# LMAT_AMT_V2.net
KiCad netlist of a schematic drawn in Altium Designer
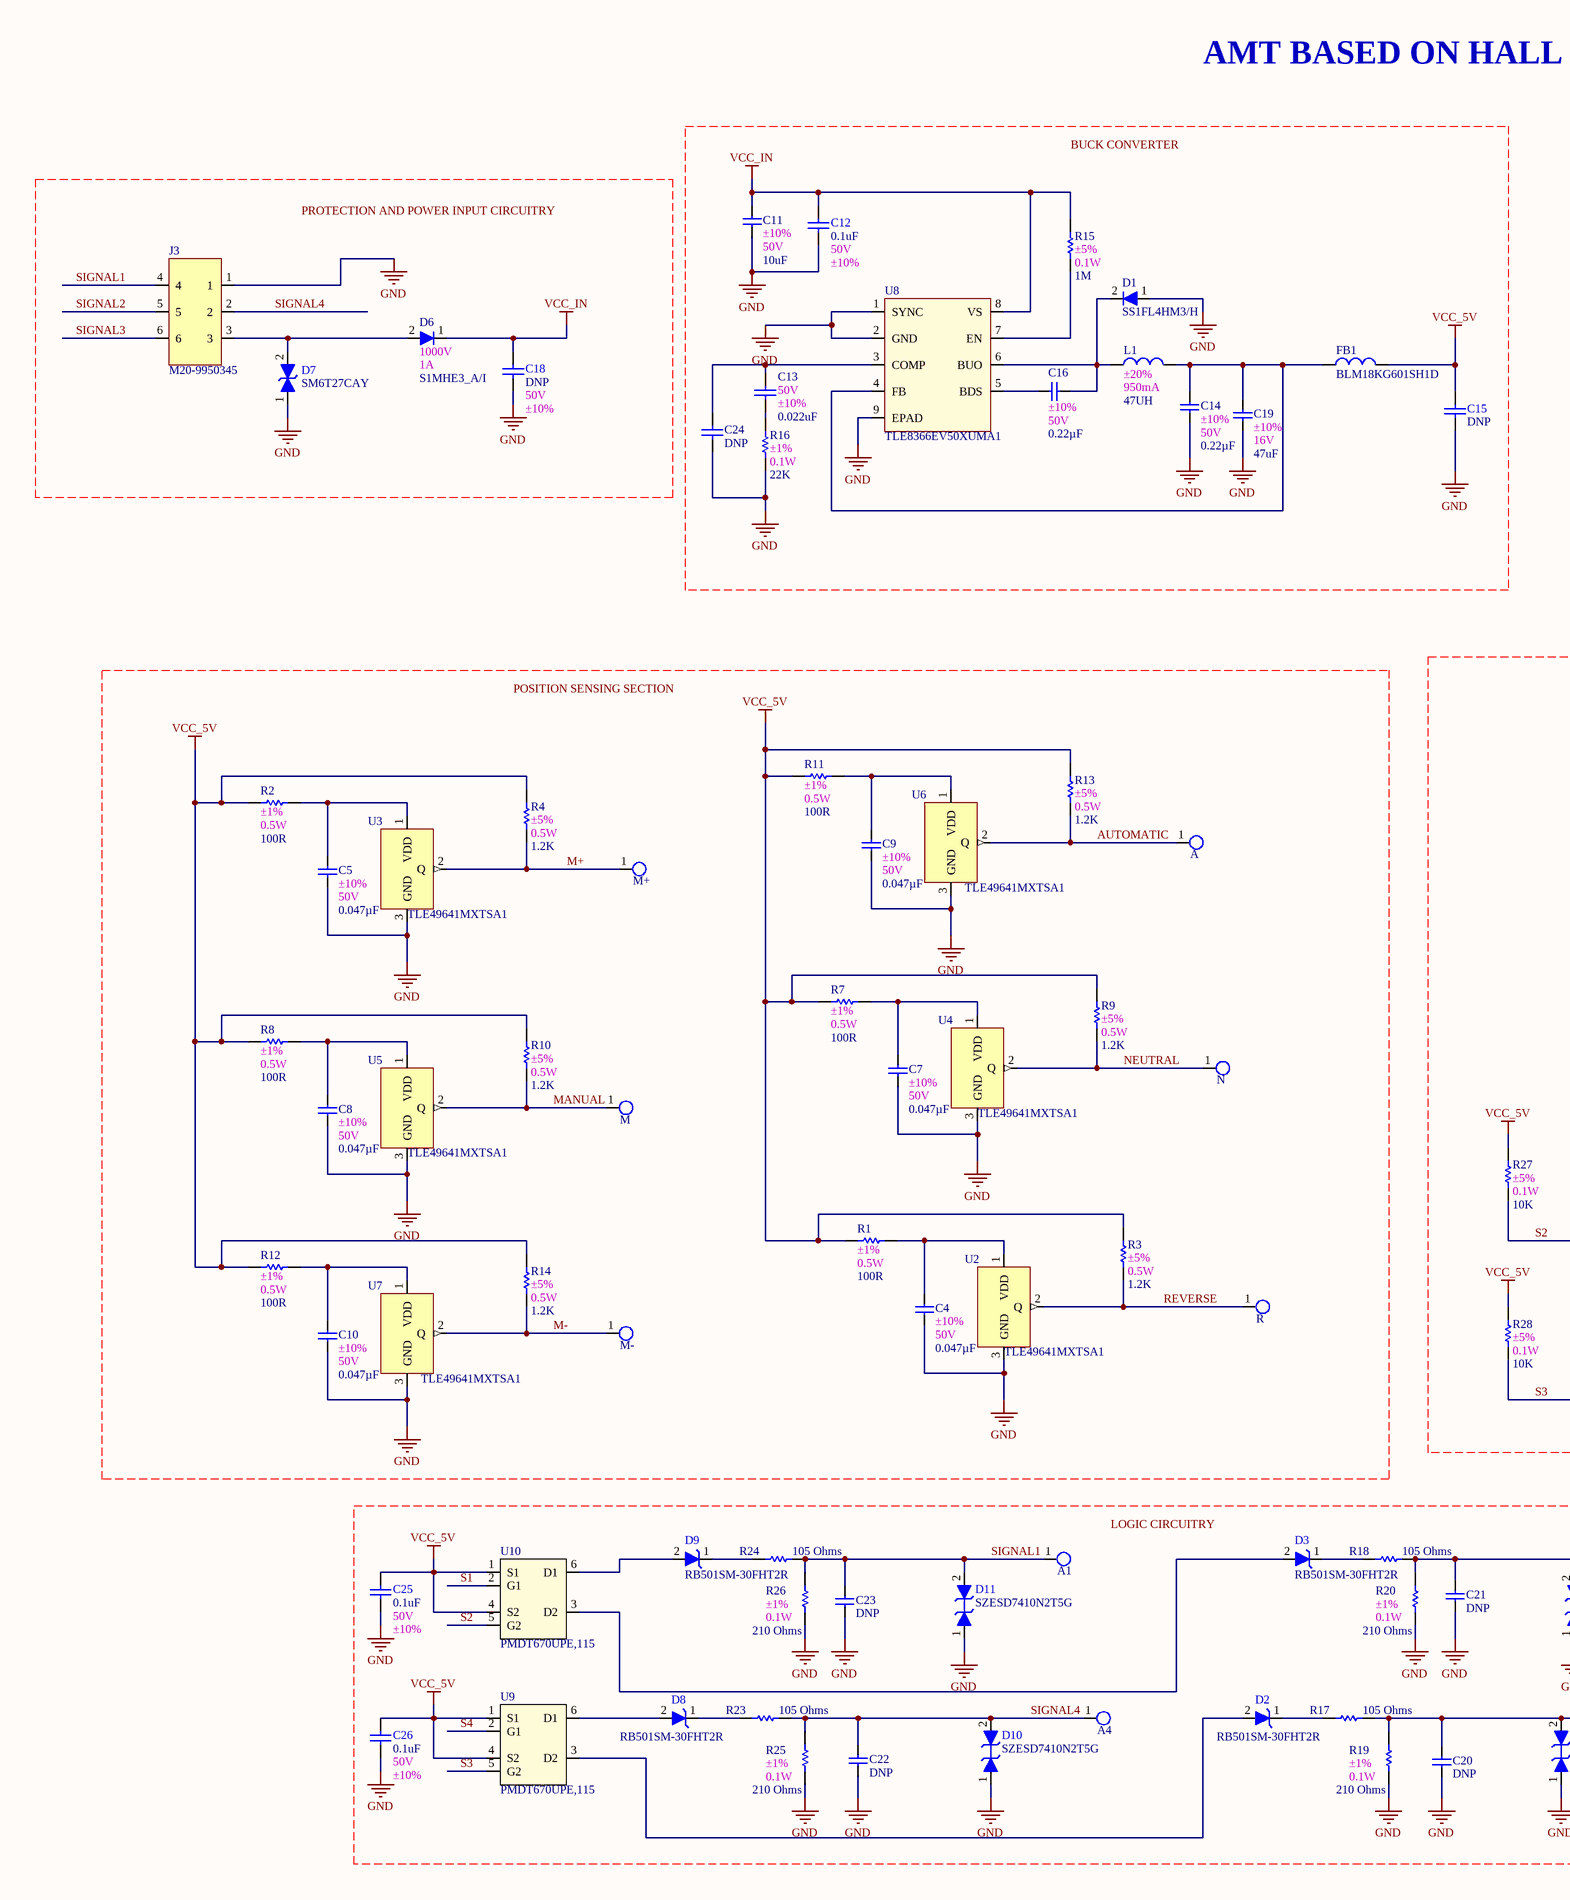
[diagram p0: LMAT_AMT_V2.SchDoc, left]
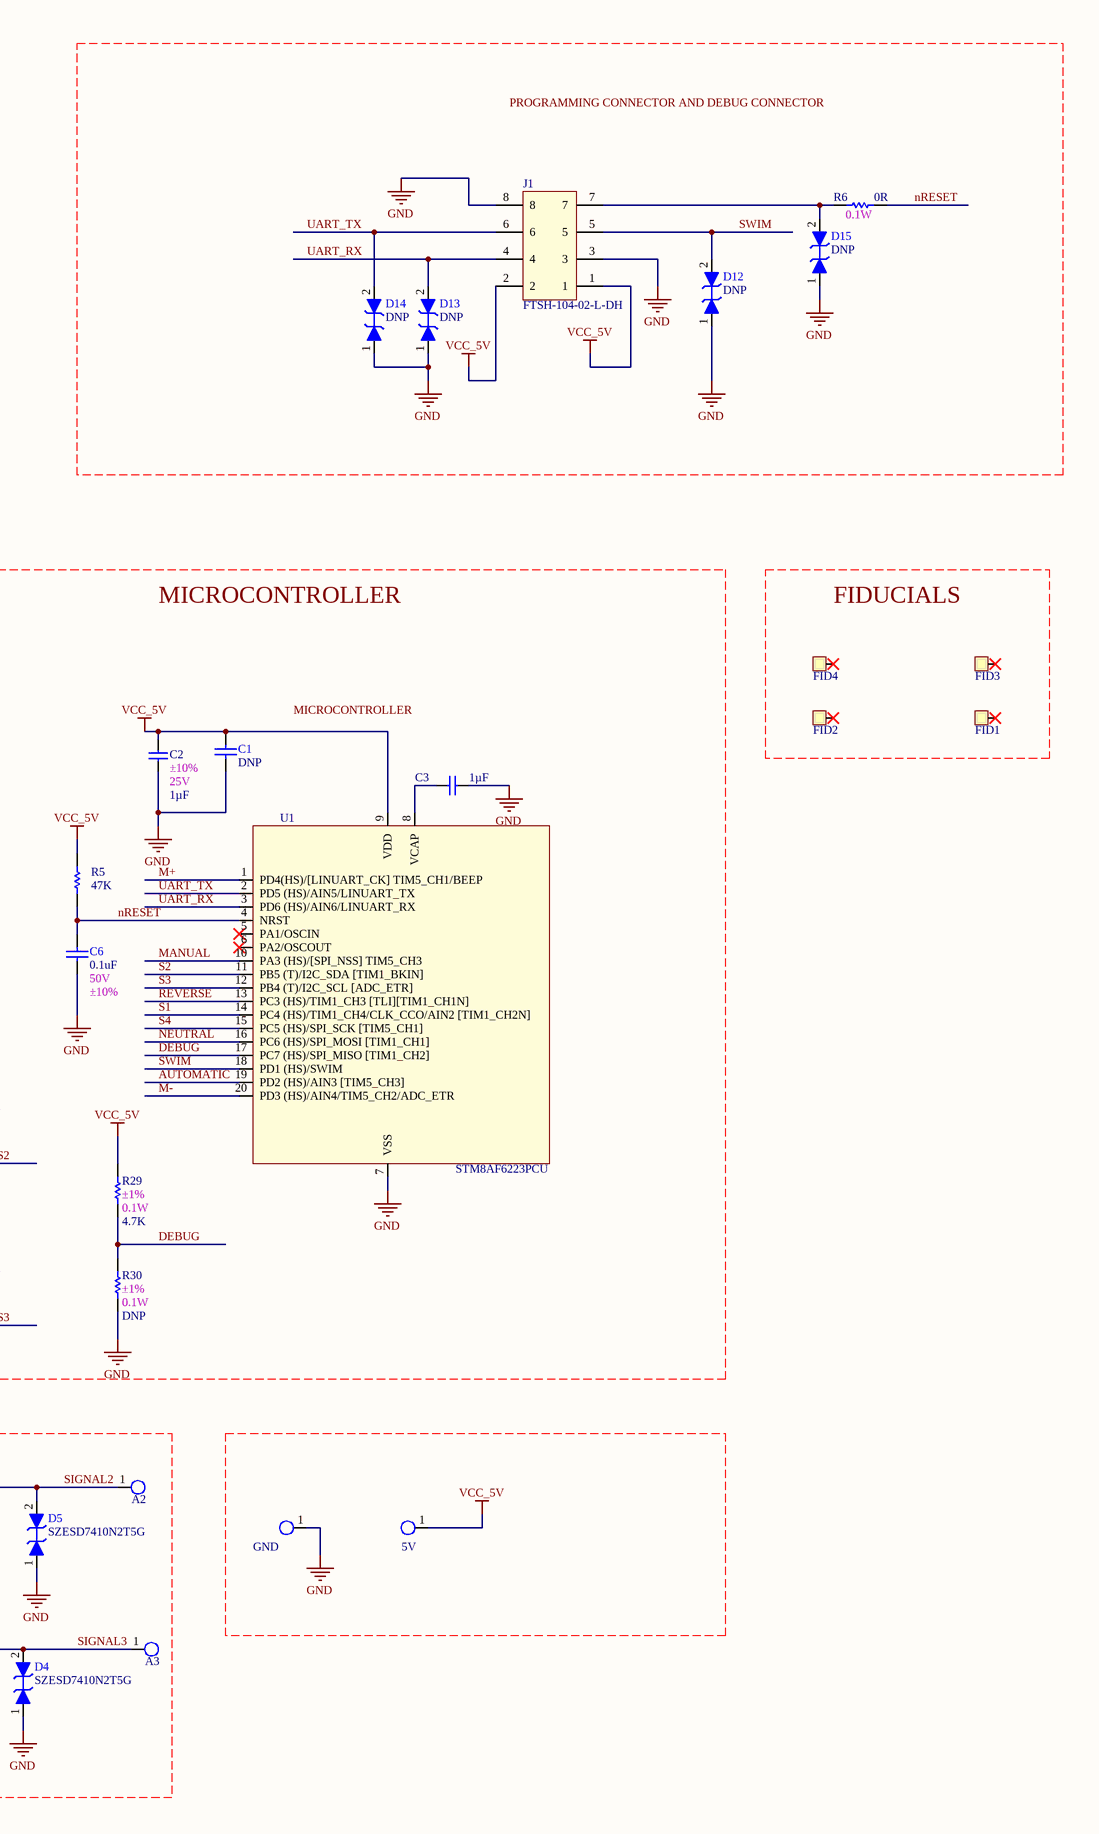
[diagram p1: LMAT_AMT_V2.SchDoc, right]

(export (version "E")
  (design (tool "Eeschema 10.0.6"))
  (components
    (comp (ref "5V")
      (value "Test Point- 35mil")
      (footprint "Integrated_Master_Library:TP_35M_DIA")
      (fields (field (name "INTERNAL PART NUMBER") "EMS-TP35MIL-S"))
      (libsource (lib "Integrated_Master_Library") (part "EMS-TP35MIL-S"))
    )
    (comp (ref "A")
      (value "Test Point- 35mil")
      (footprint "Integrated_Master_Library:TP_35M_DIA")
      (fields (field (name "INTERNAL PART NUMBER") "EMS-TP35MIL-S"))
      (libsource (lib "Integrated_Master_Library") (part "EMS-TP35MIL-S"))
    )
    (comp (ref "A1")
      (value "Test Point- 35mil")
      (footprint "Integrated_Master_Library:TP_35M_DIA")
      (fields (field (name "INTERNAL PART NUMBER") "EMS-TP35MIL-S"))
      (libsource (lib "Integrated_Master_Library") (part "EMS-TP35MIL-S"))
    )
    (comp (ref "A2")
      (value "Test Point- 35mil")
      (footprint "Integrated_Master_Library:TP_35M_DIA")
      (fields (field (name "INTERNAL PART NUMBER") "EMS-TP35MIL-S"))
      (libsource (lib "Integrated_Master_Library") (part "EMS-TP35MIL-S"))
    )
    (comp (ref "A3")
      (value "Test Point- 35mil")
      (footprint "Integrated_Master_Library:TP_35M_DIA")
      (fields (field (name "INTERNAL PART NUMBER") "EMS-TP35MIL-S"))
      (libsource (lib "Integrated_Master_Library") (part "EMS-TP35MIL-S"))
    )
    (comp (ref "A4")
      (value "Test Point- 35mil")
      (footprint "Integrated_Master_Library:TP_35M_DIA")
      (fields (field (name "INTERNAL PART NUMBER") "EMS-TP35MIL-S"))
      (libsource (lib "Integrated_Master_Library") (part "EMS-TP35MIL-S"))
    )
    (comp (ref "C1")
      (value "DNP")
      (footprint "SMDC0603")
      (description "CAP CER 0.1UF 50V 10% X7R 0603")
      (fields
        (field (name "MANUFACTURER PART NUMBER") "CGA3E2X7R1H104K080AA")
        (field (name "MANUFACTURER") "TDK Corporation")
      )
      (libsource (lib "Integrated_Master_Library") (part "ECA0U10K50V0-SC"))
    )
    (comp (ref "C2")
      (value "1µF")
      (footprint "Automobile-ML:SMDC0603")
      (description "CAP CER 1UF 25V X7R 0603")
      (fields
        (field (name "MANUFACTURER") "TDK Corporation")
        (field (name "VENDOR PART NUMBER") "445-173628-1-ND")
        (field (name "2ND AUXILIARY FIELD") "±10%")
        (field (name "1ST AUXILIARY FIELD") "25V")
      )
      (libsource (lib "Integrated_Master_Library (3)") (part "ECA1U00L25V0-SC"))
    )
    (comp (ref "C3")
      (value "1µF")
      (footprint "Automobile-ML:SMDC0603")
      (description "CAP CER 1UF 25V X7R 0603")
      (fields
        (field (name "MANUFACTURER") "TDK Corporation")
        (field (name "VENDOR PART NUMBER") "445-173628-1-ND")
      )
      (libsource (lib "Integrated_Master_Library (3)") (part "ECA1U00L25V0-SC"))
    )
    (comp (ref "C4")
      (value "0.047µF")
      (footprint "SMDC0603")
      (description "CAP CER 0.047UF 50V X7R 0603")
      (fields
        (field (name "MANUFACTURER") "TDK Corporation")
        (field (name "VENDOR PART NUMBER") "445-5664-1-ND")
        (field (name "2ND AUXILIARY FIELD") "±10%")
        (field (name "1ST AUXILIARY FIELD") "50V")
      )
      (libsource (lib "Integrated_Master_Library") (part "ECA47N0L50V-SC"))
    )
    (comp (ref "C5")
      (value "0.047µF")
      (footprint "SMDC0603")
      (description "CAP CER 0.047UF 50V X7R 0603")
      (fields
        (field (name "MANUFACTURER") "TDK Corporation")
        (field (name "VENDOR PART NUMBER") "445-5664-1-ND")
        (field (name "2ND AUXILIARY FIELD") "±10%")
        (field (name "1ST AUXILIARY FIELD") "50V")
      )
      (libsource (lib "Integrated_Master_Library") (part "ECA47N0L50V-SC"))
    )
    (comp (ref "C6")
      (value "0.1uF")
      (footprint "SMDC0603")
      (description "CAP CER 0.1UF 50V 10% X7R 0603")
      (fields
        (field (name "MANUFACTURER PART NUMBER") "CGA3E2X7R1H104K080AA")
        (field (name "MANUFACTURER") "TDK Corporation")
        (field (name "1ST AUXILIARY FIELD") "50V")
        (field (name "2ND AUXILIARY FIELD") "±10%")
      )
      (libsource (lib "Integrated_Master_Library") (part "ECA0U10K50V0-SC"))
    )
    (comp (ref "C7")
      (value "0.047µF")
      (footprint "SMDC0603")
      (description "CAP CER 0.047UF 50V X7R 0603")
      (fields
        (field (name "MANUFACTURER") "TDK Corporation")
        (field (name "VENDOR PART NUMBER") "445-5664-1-ND")
        (field (name "2ND AUXILIARY FIELD") "±10%")
        (field (name "1ST AUXILIARY FIELD") "50V")
      )
      (libsource (lib "Integrated_Master_Library") (part "ECA47N0L50V-SC"))
    )
    (comp (ref "C8")
      (value "0.047µF")
      (footprint "SMDC0603")
      (description "CAP CER 0.047UF 50V X7R 0603")
      (fields
        (field (name "MANUFACTURER") "TDK Corporation")
        (field (name "VENDOR PART NUMBER") "445-5664-1-ND")
        (field (name "2ND AUXILIARY FIELD") "±10%")
        (field (name "1ST AUXILIARY FIELD") "50V")
      )
      (libsource (lib "Integrated_Master_Library") (part "ECA47N0L50V-SC"))
    )
    (comp (ref "C9")
      (value "0.047µF")
      (footprint "SMDC0603")
      (description "CAP CER 0.047UF 50V X7R 0603")
      (fields
        (field (name "MANUFACTURER") "TDK Corporation")
        (field (name "VENDOR PART NUMBER") "445-5664-1-ND")
        (field (name "2ND AUXILIARY FIELD") "±10%")
        (field (name "1ST AUXILIARY FIELD") "50V")
      )
      (libsource (lib "Integrated_Master_Library") (part "ECA47N0L50V-SC"))
    )
    (comp (ref "C10")
      (value "0.047µF")
      (footprint "SMDC0603")
      (description "CAP CER 0.047UF 50V X7R 0603")
      (fields
        (field (name "MANUFACTURER") "TDK Corporation")
        (field (name "VENDOR PART NUMBER") "445-5664-1-ND")
        (field (name "2ND AUXILIARY FIELD") "±10%")
        (field (name "1ST AUXILIARY FIELD") "50V")
      )
      (libsource (lib "Integrated_Master_Library") (part "ECA47N0L50V-SC"))
    )
    (comp (ref "C11")
      (value "10uF")
      (footprint "Integrated_Master_Library:SMDC1210")
      (description "CAP CER 10UF 50V X7R 1210")
      (fields
        (field (name "MANUFACTURER") "Taiyo Yuden")
        (field (name "VENDOR PART NUMBER") "587-6026-1-ND")
        (field (name "2ND AUXILIARY FIELD") "±10%")
        (field (name "1ST AUXILIARY FIELD") "50V")
      )
      (libsource (lib "AMT") (part "ECA10U0L50V0-SH"))
    )
    (comp (ref "C12")
      (value "0.1uF")
      (footprint "SMDC0603")
      (description "CAP CER 0.1UF 50V 10% X7R 0603")
      (fields
        (field (name "MANUFACTURER PART NUMBER") "CGA3E2X7R1H104K080AA")
        (field (name "MANUFACTURER") "TDK Corporation")
        (field (name "1ST AUXILIARY FIELD") "50V")
        (field (name "2ND AUXILIARY FIELD") "±10%")
      )
      (libsource (lib "Integrated_Master_Library") (part "ECA0U10K50V0-SC"))
    )
    (comp (ref "C13")
      (value "0.022uF")
      (footprint "SMDC0603")
      (description "CAP CER 0.022UF 50V 10% X7R 0603")
      (fields
        (field (name "MANUFACTURER PART NUMBER") "CGA3E2X7R1H223K080AA")
        (field (name "MANUFACTURER") "TDK Corporation")
        (field (name "1ST AUXILIARY FIELD") "50V")
        (field (name "2ND AUXILIARY FIELD") "±10%")
      )
      (libsource (lib "Integrated_Master_Library") (part "ECA0U022K50V0-SC"))
    )
    (comp (ref "C14")
      (value "0.22µF")
      (footprint "Automobile-ML:SMDC0603")
      (description "CAP CER 0.22UF 50V X7R 0603")
      (fields
        (field (name "MANUFACTURER") "Murata Electronics North America")
        (field (name "VENDOR PART NUMBER") "490-14410-1-ND")
        (field (name "2ND AUXILIARY FIELD") "±10%")
        (field (name "1ST AUXILIARY FIELD") "50V")
      )
      (libsource (lib "Integrated_Master_Library (3)") (part "ECA0U22L50V0-SC"))
    )
    (comp (ref "C15")
      (value "DNP")
      (footprint "SMDC0603")
      (description "CAP CER 0.1UF 50V 10% X7R 0603")
      (fields
        (field (name "MANUFACTURER PART NUMBER") "CGA3E2X7R1H104K080AA")
        (field (name "MANUFACTURER") "TDK Corporation")
      )
      (libsource (lib "Integrated_Master_Library") (part "ECA0U10K50V0-SC"))
    )
    (comp (ref "C16")
      (value "0.22µF")
      (footprint "SMDC0603")
      (description "CAP CER 0.22UF 50V X7R 0603")
      (fields
        (field (name "MANUFACTURER") "Murata Electronics North America")
        (field (name "VENDOR PART NUMBER") "490-14410-1-ND")
        (field (name "2ND AUXILIARY FIELD") "±10%")
        (field (name "1ST AUXILIARY FIELD") "50V")
      )
      (libsource (lib "Integrated_Master_Library") (part "ECA0U22L50V0-SC"))
    )
    (comp (ref "C18")
      (value "DNP")
      (footprint "SMDC0603")
      (description "CAP CER 0.1UF 50V 10% X7R 0603")
      (fields
        (field (name "MANUFACTURER PART NUMBER") "CGA3E2X7R1H104K080AA")
        (field (name "MANUFACTURER") "TDK Corporation")
        (field (name "1ST AUXILIARY FIELD") "50V")
        (field (name "2ND AUXILIARY FIELD") "±10%")
      )
      (libsource (lib "Integrated_Master_Library") (part "ECA0U10K50V0-SC"))
    )
    (comp (ref "C19")
      (value "47uF")
      (footprint "SMDC1210")
      (description "CAP CER 47UF 16V X6S 1210")
      (fields
        (field (name "MANUFACTURER") "Murata Electronics North America")
        (field (name "VENDOR PART NUMBER") "490-12494-1-ND")
        (field (name "2ND AUXILIARY FIELD") "±10%")
        (field (name "1ST AUXILIARY FIELD") "16V")
      )
      (libsource (lib "Automobile-ML") (part "ECA47U0L16V0-SH"))
    )
    (comp (ref "C20")
      (value "DNP")
      (footprint "SMDC0603")
      (description "CAP CER 10000PF 50V X8R 0603")
      (fields
        (field (name "MANUFACTURER") "TDK Corporation")
        (field (name "VENDOR PART NUMBER") "445-5892-1-ND")
      )
      (libsource (lib "Automobile-ML") (part "ECA0U01L50V0-SC"))
    )
    (comp (ref "C21")
      (value "DNP")
      (footprint "SMDC0603")
      (description "CAP CER 10000PF 50V X8R 0603")
      (fields
        (field (name "MANUFACTURER") "TDK Corporation")
        (field (name "VENDOR PART NUMBER") "445-5892-1-ND")
      )
      (libsource (lib "Automobile-ML") (part "ECA0U01L50V0-SC"))
    )
    (comp (ref "C22")
      (value "DNP")
      (footprint "SMDC0603")
      (description "CAP CER 10000PF 50V X8R 0603")
      (fields
        (field (name "MANUFACTURER") "TDK Corporation")
        (field (name "VENDOR PART NUMBER") "445-5892-1-ND")
      )
      (libsource (lib "Automobile-ML") (part "ECA0U01L50V0-SC"))
    )
    (comp (ref "C23")
      (value "DNP")
      (footprint "SMDC0603")
      (description "CAP CER 10000PF 50V X8R 0603")
      (fields
        (field (name "MANUFACTURER") "TDK Corporation")
        (field (name "VENDOR PART NUMBER") "445-5892-1-ND")
      )
      (libsource (lib "Automobile-ML") (part "ECA0U01L50V0-SC"))
    )
    (comp (ref "C24")
      (value "DNP")
      (footprint "SMDC0603")
      (description "CAP CER 0.022UF 50V 10% X7R 0603")
      (fields
        (field (name "MANUFACTURER PART NUMBER") "CGA3E2X7R1H223K080AA")
        (field (name "MANUFACTURER") "TDK Corporation")
      )
      (libsource (lib "Integrated_Master_Library") (part "ECA0U022K50V0-SC"))
    )
    (comp (ref "C25")
      (value "0.1uF")
      (footprint "SMDC0603")
      (description "CAP CER 0.1UF 50V 10% X7R 0603")
      (fields
        (field (name "MANUFACTURER PART NUMBER") "CGA3E2X7R1H104K080AA")
        (field (name "MANUFACTURER") "TDK Corporation")
        (field (name "1ST AUXILIARY FIELD") "50V")
        (field (name "2ND AUXILIARY FIELD") "±10%")
      )
      (libsource (lib "Integrated_Master_Library") (part "ECA0U10K50V0-SC"))
    )
    (comp (ref "C26")
      (value "0.1uF")
      (footprint "SMDC0603")
      (description "CAP CER 0.1UF 50V 10% X7R 0603")
      (fields
        (field (name "MANUFACTURER PART NUMBER") "CGA3E2X7R1H104K080AA")
        (field (name "MANUFACTURER") "TDK Corporation")
        (field (name "1ST AUXILIARY FIELD") "50V")
        (field (name "2ND AUXILIARY FIELD") "±10%")
      )
      (libsource (lib "Integrated_Master_Library") (part "ECA0U10K50V0-SC"))
    )
    (comp (ref "D1")
      (value "SS1FL4HM3/H")
      (footprint "Integrated_Master_Library:SODFL370X110-2N")
      (description "DIODE SCHOTTKY 40V 1A DO-219AB")
      (fields
        (field (name "MANUFACTURER") "Vishay Semiconductor Diodes Division")
        (field (name "INTERNAL PART NUMBER") "EDDVS1A0040V0-S")
      )
      (libsource (lib "Integrated_Master_Library (3)") (part "EDDVS1A0040V0-S"))
    )
    (comp (ref "D2")
      (value "RB501SM-30FHT2R")
      (footprint "Integrated_Master_Library:SOD1700X70N-V2")
      (description "Diode Schottky 30V 100mA Surface Mount EMD2")
      (fields
        (field (name "MANUFACTURER") "Rohm Semiconductor")
        (field (name "INTERNAL PART NUMBER") "EDDR0A1030V0-S")
      )
      (libsource (lib "Integrated_Master_Library (3)") (part "EDDR0A1030V0-S"))
    )
    (comp (ref "D3")
      (value "RB501SM-30FHT2R")
      (footprint "Integrated_Master_Library:SOD1700X70N-V2")
      (description "Diode Schottky 30V 100mA Surface Mount EMD2")
      (fields
        (field (name "MANUFACTURER") "Rohm Semiconductor")
        (field (name "INTERNAL PART NUMBER") "EDDR0A1030V0-S")
      )
      (libsource (lib "Integrated_Master_Library (3)") (part "EDDR0A1030V0-S"))
    )
    (comp (ref "D4")
      (value "SZESD7410N2T5G")
      (footprint "DFN65P100X65X45-2N")
      (description "TVS DIODE 8V 20V 2X2DFN")
      (fields
        (field (name "MANUFACTURER") "ON Semiconductor")
        (field (name "INTERNAL PART NUMBER") "EDDOS16A010V0-S")
      )
      (libsource (lib "Automobile-ML") (part "EDDOS16A010V0-S"))
    )
    (comp (ref "D5")
      (value "SZESD7410N2T5G")
      (footprint "DFN65P100X65X45-2N")
      (description "TVS DIODE 8V 20V 2X2DFN")
      (fields
        (field (name "MANUFACTURER") "ON Semiconductor")
        (field (name "INTERNAL PART NUMBER") "EDDOS16A010V0-S")
      )
      (libsource (lib "Automobile-ML") (part "EDDOS16A010V0-S"))
    )
    (comp (ref "D6")
      (value "S1MHE3_A/I")
      (footprint "Integrated_Master_Library:DIOM4227X23N-2N")
      (description "DIODE GEN PURP 1KV 1A DO214AC")
      (fields
        (field (name "MANUFACTURER") "Vishay Semiconductor Diodes Division")
        (field (name "INTERNAL PART NUMBER") "EDDVS1A001000V-S")
        (field (name "1ST AUXILIARY FIELD") "1000V")
        (field (name "2ND AUXILIARY FIELD") "1A")
      )
      (libsource (lib "Integrated_Master_Library") (part "EDDVS1A001000V-S"))
    )
    (comp (ref "D7")
      (value "SM6T27CAY")
      (footprint "DIOM4336X26B")
      (description "TVS DIODE 23.1V 48.3V SMB")
      (fields
        (field (name "MANUFACTURER") "STMicroelectronics")
        (field (name "INTERNAL PART NUMBER") "EDDST83A025V7-S")
      )
      (libsource (lib "Integrated_Master_Library") (part "EDDST83A025V7-S"))
    )
    (comp (ref "D8")
      (value "RB501SM-30FHT2R")
      (footprint "Integrated_Master_Library:SOD1700X70N-V2")
      (description "Diode Schottky 30V 100mA Surface Mount EMD2")
      (fields
        (field (name "MANUFACTURER") "Rohm Semiconductor")
        (field (name "INTERNAL PART NUMBER") "EDDR0A1030V0-S")
      )
      (libsource (lib "Integrated_Master_Library (3)") (part "EDDR0A1030V0-S"))
    )
    (comp (ref "D9")
      (value "RB501SM-30FHT2R")
      (footprint "Integrated_Master_Library:SOD1700X70N-V2")
      (description "Diode Schottky 30V 100mA Surface Mount EMD2")
      (fields
        (field (name "MANUFACTURER") "Rohm Semiconductor")
        (field (name "INTERNAL PART NUMBER") "EDDR0A1030V0-S")
      )
      (libsource (lib "Integrated_Master_Library (3)") (part "EDDR0A1030V0-S"))
    )
    (comp (ref "D10")
      (value "SZESD7410N2T5G")
      (footprint "DFN65P100X65X45-2N")
      (description "TVS DIODE 8V 20V 2X2DFN")
      (fields
        (field (name "MANUFACTURER") "ON Semiconductor")
        (field (name "INTERNAL PART NUMBER") "EDDOS16A010V0-S")
      )
      (libsource (lib "Automobile-ML") (part "EDDOS16A010V0-S"))
    )
    (comp (ref "D11")
      (value "SZESD7410N2T5G")
      (footprint "DFN65P100X65X45-2N")
      (description "TVS DIODE 8V 20V 2X2DFN")
      (fields
        (field (name "MANUFACTURER") "ON Semiconductor")
        (field (name "INTERNAL PART NUMBER") "EDDOS16A010V0-S")
      )
      (libsource (lib "Automobile-ML") (part "EDDOS16A010V0-S"))
    )
    (comp (ref "D12")
      (value "DNP")
      (footprint "DFN65P100X65X45-2N")
      (description "TVS DIODE 8V 20V 2X2DFN")
      (fields
        (field (name "MANUFACTURER PART NUMBER") "SZESD7410N2T5G")
        (field (name "MANUFACTURER") "ON Semiconductor")
      )
      (libsource (lib "Automobile-ML") (part "EDDOS16A010V0-S"))
    )
    (comp (ref "D13")
      (value "DNP")
      (footprint "DFN65P100X65X45-2N")
      (description "TVS DIODE 8V 20V 2X2DFN")
      (fields
        (field (name "MANUFACTURER PART NUMBER") "SZESD7410N2T5G")
        (field (name "MANUFACTURER") "ON Semiconductor")
      )
      (libsource (lib "Automobile-ML") (part "EDDOS16A010V0-S"))
    )
    (comp (ref "D14")
      (value "DNP")
      (footprint "DFN65P100X65X45-2N")
      (description "TVS DIODE 8V 20V 2X2DFN")
      (fields
        (field (name "MANUFACTURER PART NUMBER") "SZESD7410N2T5G")
        (field (name "MANUFACTURER") "ON Semiconductor")
      )
      (libsource (lib "Automobile-ML") (part "EDDOS16A010V0-S"))
    )
    (comp (ref "D15")
      (value "DNP")
      (footprint "DFN65P100X65X45-2N")
      (description "TVS DIODE 8V 20V 2X2DFN")
      (fields
        (field (name "MANUFACTURER PART NUMBER") "SZESD7410N2T5G")
        (field (name "MANUFACTURER") "ON Semiconductor")
      )
      (libsource (lib "Automobile-ML") (part "EDDOS16A010V0-S"))
    )
    (comp (ref "FB1")
      (value "BLM18KG601SH1D")
      (footprint "Integrated_Master_Library:SMDL0603")
      (description "FERRITE BEAD 600 OHM 0603 1LN")
      (fields
        (field (name "MANUFACTURER") "Murata Electronics North America")
        (field (name "VENDOR PART NUMBER") "490-13259-1-ND")
      )
      (libsource (lib "Automobile-ML") (part "EIN600R1A30-S"))
    )
    (comp (ref "FID1")
      (value "FID40X40")
      (footprint "FID40X40")
      (libsource (lib "Integrated_Master_Library") (part "FID_40X40"))
    )
    (comp (ref "FID2")
      (value "FID40X40")
      (footprint "FID40X40")
      (libsource (lib "Integrated_Master_Library") (part "FID_40X40"))
    )
    (comp (ref "FID3")
      (value "FID40X40")
      (footprint "FID40X40")
      (libsource (lib "Integrated_Master_Library") (part "FID_40X40"))
    )
    (comp (ref "FID4")
      (value "FID40X40")
      (footprint "FID40X40")
      (libsource (lib "Integrated_Master_Library") (part "FID_40X40"))
    )
    (comp (ref "GND")
      (value "Test Point- 35mil")
      (footprint "Integrated_Master_Library:TP_35M_DIA")
      (fields (field (name "INTERNAL PART NUMBER") "EMS-TP35MIL-S"))
      (libsource (lib "Integrated_Master_Library") (part "EMS-TP35MIL-S"))
    )
    (comp (ref "J1")
      (value "CONN HEADER R/A 6POS 2.54MMCONN HEADER SMD R/A 8POS 1.27MM")
      (footprint "HDRRA8W53P127_2X4_9754X251X343P")
      (description "CONN HEADER SMD R/A 8POS 1.27MM")
      (fields
        (field (name "MANUFACTURER") "Samtec Inc.")
        (field (name "INTERNAL PART NUMBER") "ECN-FTSH-104-02-L-DH-0005")
        (field (name "MANUFACTURER PART NUMBER") "FTSH-104-02-L-DH")
      )
      (libsource (lib "Automobile-ML") (part "ECN-FTSH-104-02-L-DH-0005"))
    )
    (comp (ref "J3")
      (value "CONN HEADER R/A 6POS 2.54MM")
      (footprint "HDRRA6W86P254_2X3_1344X254X528P")
      (fields
        (field (name "MANUFACTURER") "Harwin Inc.")
        (field (name "INTERNAL PART NUMBER") "ECN-M20-9950345-0003")
        (field (name "VENDOR PART NUMBER") "952-2092-ND")
        (field (name "MANUFACTURER PART NUMBER") "M20-9950345")
      )
      (libsource (lib "Automobile-ML") (part "ECN-M20-9950345-0003"))
    )
    (comp (ref "L1")
      (value "47UH")
      (footprint "Integrated_Master_Library:INDC4949X310N")
      (description "FIXED IND 47UH 700MA 422.5 MOHM")
      (fields
        (field (name "MANUFACTURER") "Taiyo Yuden")
        (field (name "VENDOR PART NUMBER") "587-3604-1-ND")
        (field (name "2ND AUXILIARY FIELD") "±20%")
        (field (name "1ST AUXILIARY FIELD") "950mA")
      )
      (libsource (lib "AMT") (part "EIN47U0N950M-S"))
    )
    (comp (ref "M")
      (value "Test Point- 35mil")
      (footprint "Integrated_Master_Library:TP_35M_DIA")
      (fields (field (name "INTERNAL PART NUMBER") "EMS-TP35MIL-S"))
      (libsource (lib "Integrated_Master_Library") (part "EMS-TP35MIL-S"))
    )
    (comp (ref "M+")
      (value "Test Point- 35mil")
      (footprint "Integrated_Master_Library:TP_35M_DIA")
      (fields (field (name "INTERNAL PART NUMBER") "EMS-TP35MIL-S"))
      (libsource (lib "Integrated_Master_Library") (part "EMS-TP35MIL-S"))
    )
    (comp (ref "M-")
      (value "Test Point- 35mil")
      (footprint "Integrated_Master_Library:TP_35M_DIA")
      (fields (field (name "INTERNAL PART NUMBER") "EMS-TP35MIL-S"))
      (libsource (lib "Integrated_Master_Library") (part "EMS-TP35MIL-S"))
    )
    (comp (ref "N")
      (value "Test Point- 35mil")
      (footprint "Integrated_Master_Library:TP_35M_DIA")
      (fields (field (name "INTERNAL PART NUMBER") "EMS-TP35MIL-S"))
      (libsource (lib "Integrated_Master_Library") (part "EMS-TP35MIL-S"))
    )
    (comp (ref "R")
      (value "Test Point- 35mil")
      (footprint "Integrated_Master_Library:TP_35M_DIA")
      (fields (field (name "INTERNAL PART NUMBER") "EMS-TP35MIL-S"))
      (libsource (lib "Integrated_Master_Library") (part "EMS-TP35MIL-S"))
    )
    (comp (ref "R1")
      (value "100R")
      (footprint "Integrated_Master_Library:SMDR0805")
      (description "RES SMD 100 OHM 1% 1/2W 0805")
      (fields
        (field (name "MANUFACTURER PART NUMBER") "ERJ-P06F1000V")
        (field (name "MANUFACTURER") "Panasonic Electronic Components")
        (field (name "2ND AUXILIARY FIELD") "±1%")
        (field (name "1ST AUXILIARY FIELD") "0.5W")
      )
      (libsource (lib "AMT") (part "ERE100RG120-SE"))
    )
    (comp (ref "R2")
      (value "100R")
      (footprint "Integrated_Master_Library:SMDR0805")
      (description "RES SMD 100 OHM 1% 1/2W 0805")
      (fields
        (field (name "MANUFACTURER PART NUMBER") "ERJ-P06F1000V")
        (field (name "MANUFACTURER") "Panasonic Electronic Components")
        (field (name "2ND AUXILIARY FIELD") "±1%")
        (field (name "1ST AUXILIARY FIELD") "0.5W")
      )
      (libsource (lib "AMT") (part "ERE100RG120-SE"))
    )
    (comp (ref "R3")
      (value "1.2K")
      (footprint "SMDR0805")
      (description "RES SMD 1.2K OHM 5% 1/2W 0805")
      (fields
        (field (name "MANUFACTURER") "Panasonic Electronic Components")
        (field (name "VENDOR PART NUMBER") "P1.2KADCT-ND")
        (field (name "2ND AUXILIARY FIELD") "±5%")
        (field (name "1ST AUXILIARY FIELD") "0.5W")
      )
      (libsource (lib "Integrated_Master_Library") (part "ERE1K20G102-SE"))
    )
    (comp (ref "R4")
      (value "1.2K")
      (footprint "SMDR0805")
      (description "RES SMD 1.2K OHM 5% 1/2W 0805")
      (fields
        (field (name "MANUFACTURER") "Panasonic Electronic Components")
        (field (name "VENDOR PART NUMBER") "P1.2KADCT-ND")
        (field (name "2ND AUXILIARY FIELD") "±5%")
        (field (name "1ST AUXILIARY FIELD") "0.5W")
      )
      (libsource (lib "Integrated_Master_Library") (part "ERE1K20G102-SE"))
    )
    (comp (ref "R5")
      (value "47K")
      (footprint "Automobile-ML:SMDR0603")
      (description "RES SMD 47K OHM 1% 1/10W 0603")
      (fields (field (name "MANUFACTURER") "Yageo") (field (name "VENDOR PART NUMBER") "YAG2129CT-ND"))
      (libsource (lib "Integrated_Master_Library (3)") (part "ERE47K0G110-SC"))
    )
    (comp (ref "R6")
      (value "0R")
      (footprint "SMDR0603")
      (description "RES SMD 0.0OHM JUMPER 1/10W 0603")
      (fields
        (field (name "MANUFACTURER PART NUMBER") "ERJ-3GEY0R00V")
        (field (name "MANUFACTURER") "Panasonic Electronic Components")
        (field (name "1ST AUXILIARY FIELD") "0.1W")
      )
      (libsource (lib "Integrated_Master_Library") (part "ERE0R00110-SC"))
    )
    (comp (ref "R7")
      (value "100R")
      (footprint "Integrated_Master_Library:SMDR0805")
      (description "RES SMD 100 OHM 1% 1/2W 0805")
      (fields
        (field (name "MANUFACTURER PART NUMBER") "ERJ-P06F1000V")
        (field (name "MANUFACTURER") "Panasonic Electronic Components")
        (field (name "2ND AUXILIARY FIELD") "±1%")
        (field (name "1ST AUXILIARY FIELD") "0.5W")
      )
      (libsource (lib "AMT") (part "ERE100RG120-SE"))
    )
    (comp (ref "R8")
      (value "100R")
      (footprint "Integrated_Master_Library:SMDR0805")
      (description "RES SMD 100 OHM 1% 1/2W 0805")
      (fields
        (field (name "MANUFACTURER PART NUMBER") "ERJ-P06F1000V")
        (field (name "MANUFACTURER") "Panasonic Electronic Components")
        (field (name "2ND AUXILIARY FIELD") "±1%")
        (field (name "1ST AUXILIARY FIELD") "0.5W")
      )
      (libsource (lib "AMT") (part "ERE100RG120-SE"))
    )
    (comp (ref "R9")
      (value "1.2K")
      (footprint "SMDR0805")
      (description "RES SMD 1.2K OHM 5% 1/2W 0805")
      (fields
        (field (name "MANUFACTURER") "Panasonic Electronic Components")
        (field (name "VENDOR PART NUMBER") "P1.2KADCT-ND")
        (field (name "2ND AUXILIARY FIELD") "±5%")
        (field (name "1ST AUXILIARY FIELD") "0.5W")
      )
      (libsource (lib "Integrated_Master_Library") (part "ERE1K20G102-SE"))
    )
    (comp (ref "R10")
      (value "1.2K")
      (footprint "SMDR0805")
      (description "RES SMD 1.2K OHM 5% 1/2W 0805")
      (fields
        (field (name "MANUFACTURER") "Panasonic Electronic Components")
        (field (name "VENDOR PART NUMBER") "P1.2KADCT-ND")
        (field (name "2ND AUXILIARY FIELD") "±5%")
        (field (name "1ST AUXILIARY FIELD") "0.5W")
      )
      (libsource (lib "Integrated_Master_Library") (part "ERE1K20G102-SE"))
    )
    (comp (ref "R11")
      (value "100R")
      (footprint "Integrated_Master_Library:SMDR0805")
      (description "RES SMD 100 OHM 1% 1/2W 0805")
      (fields
        (field (name "MANUFACTURER PART NUMBER") "ERJ-P06F1000V")
        (field (name "MANUFACTURER") "Panasonic Electronic Components")
        (field (name "2ND AUXILIARY FIELD") "±1%")
        (field (name "1ST AUXILIARY FIELD") "0.5W")
      )
      (libsource (lib "AMT") (part "ERE100RG120-SE"))
    )
    (comp (ref "R12")
      (value "100R")
      (footprint "Integrated_Master_Library:SMDR0805")
      (description "RES SMD 100 OHM 1% 1/2W 0805")
      (fields
        (field (name "MANUFACTURER PART NUMBER") "ERJ-P06F1000V")
        (field (name "MANUFACTURER") "Panasonic Electronic Components")
        (field (name "2ND AUXILIARY FIELD") "±1%")
        (field (name "1ST AUXILIARY FIELD") "0.5W")
      )
      (libsource (lib "AMT") (part "ERE100RG120-SE"))
    )
    (comp (ref "R13")
      (value "1.2K")
      (footprint "SMDR0805")
      (description "RES SMD 1.2K OHM 5% 1/2W 0805")
      (fields
        (field (name "MANUFACTURER") "Panasonic Electronic Components")
        (field (name "VENDOR PART NUMBER") "P1.2KADCT-ND")
        (field (name "2ND AUXILIARY FIELD") "±5%")
        (field (name "1ST AUXILIARY FIELD") "0.5W")
      )
      (libsource (lib "Integrated_Master_Library") (part "ERE1K20G102-SE"))
    )
    (comp (ref "R14")
      (value "1.2K")
      (footprint "SMDR0805")
      (description "RES SMD 1.2K OHM 5% 1/2W 0805")
      (fields
        (field (name "MANUFACTURER") "Panasonic Electronic Components")
        (field (name "VENDOR PART NUMBER") "P1.2KADCT-ND")
        (field (name "2ND AUXILIARY FIELD") "±5%")
        (field (name "1ST AUXILIARY FIELD") "0.5W")
      )
      (libsource (lib "Integrated_Master_Library") (part "ERE1K20G102-SE"))
    )
    (comp (ref "R15")
      (value "1M")
      (footprint "SMDR0603")
      (description "RES SMD 1M OHM 5% 1/10W 0603")
      (fields
        (field (name "MANUFACTURER") "Vishay Dale")
        (field (name "VENDOR PART NUMBER") "541-2216-1-ND")
        (field (name "2ND AUXILIARY FIELD") "±5%")
        (field (name "1ST AUXILIARY FIELD") "0.1W")
      )
      (libsource (lib "Automobile-ML") (part "ERE1M00K110-SC"))
    )
    (comp (ref "R16")
      (value "22K")
      (footprint "SMDR0603")
      (description "RES SMD 22K OHM 1% 1/10W 0603")
      (fields
        (field (name "MANUFACTURER") "Panasonic Electronic Components")
        (field (name "VENDOR PART NUMBER") "P22.0KHCT-ND")
        (field (name "2ND AUXILIARY FIELD") "±1%")
        (field (name "1ST AUXILIARY FIELD") "0.1W")
      )
      (libsource (lib "Automobile-ML") (part "ERE22K0G110-SC"))
    )
    (comp (ref "R17")
      (value "105 Ohms")
      (footprint "SMDR0603")
      (description "RES SMD 105 OHM 1% 1/10W 0603")
      (fields
        (field (name "MANUFACTURER") "Panasonic Electronic Components")
        (field (name "VENDOR PART NUMBER") "P105HCT-ND")
      )
      (libsource (lib "Automobile-ML") (part "ERE105RG110-SC"))
    )
    (comp (ref "R18")
      (value "105 Ohms")
      (footprint "SMDR0603")
      (description "RES SMD 105 OHM 1% 1/10W 0603")
      (fields
        (field (name "MANUFACTURER") "Panasonic Electronic Components")
        (field (name "VENDOR PART NUMBER") "P105HCT-ND")
      )
      (libsource (lib "Automobile-ML") (part "ERE105RG110-SC"))
    )
    (comp (ref "R19")
      (value "210 Ohms")
      (footprint "SMDR0603")
      (description "RES SMD 210 OHM 1% 1/10W 0603")
      (fields
        (field (name "MANUFACTURER") "Panasonic Electronic Components")
        (field (name "VENDOR PART NUMBER") "P210HCT-ND")
        (field (name "2ND AUXILIARY FIELD") "±1%")
        (field (name "1ST AUXILIARY FIELD") "0.1W")
      )
      (libsource (lib "Automobile-ML") (part "ERE210RG110-SC"))
    )
    (comp (ref "R20")
      (value "210 Ohms")
      (footprint "SMDR0603")
      (description "RES SMD 210 OHM 1% 1/10W 0603")
      (fields
        (field (name "MANUFACTURER") "Panasonic Electronic Components")
        (field (name "VENDOR PART NUMBER") "P210HCT-ND")
        (field (name "2ND AUXILIARY FIELD") "±1%")
        (field (name "1ST AUXILIARY FIELD") "0.1W")
      )
      (libsource (lib "Automobile-ML") (part "ERE210RG110-SC"))
    )
    (comp (ref "R23")
      (value "105 Ohms")
      (footprint "SMDR0603")
      (description "RES SMD 105 OHM 1% 1/10W 0603")
      (fields
        (field (name "MANUFACTURER") "Panasonic Electronic Components")
        (field (name "VENDOR PART NUMBER") "P105HCT-ND")
      )
      (libsource (lib "Automobile-ML") (part "ERE105RG110-SC"))
    )
    (comp (ref "R24")
      (value "105 Ohms")
      (footprint "SMDR0603")
      (description "RES SMD 105 OHM 1% 1/10W 0603")
      (fields
        (field (name "MANUFACTURER") "Panasonic Electronic Components")
        (field (name "VENDOR PART NUMBER") "P105HCT-ND")
      )
      (libsource (lib "Automobile-ML") (part "ERE105RG110-SC"))
    )
    (comp (ref "R25")
      (value "210 Ohms")
      (footprint "SMDR0603")
      (description "RES SMD 210 OHM 1% 1/10W 0603")
      (fields
        (field (name "MANUFACTURER") "Panasonic Electronic Components")
        (field (name "VENDOR PART NUMBER") "P210HCT-ND")
        (field (name "2ND AUXILIARY FIELD") "±1%")
        (field (name "1ST AUXILIARY FIELD") "0.1W")
      )
      (libsource (lib "Automobile-ML") (part "ERE210RG110-SC"))
    )
    (comp (ref "R26")
      (value "210 Ohms")
      (footprint "SMDR0603")
      (description "RES SMD 210 OHM 1% 1/10W 0603")
      (fields
        (field (name "MANUFACTURER") "Panasonic Electronic Components")
        (field (name "VENDOR PART NUMBER") "P210HCT-ND")
        (field (name "2ND AUXILIARY FIELD") "±1%")
        (field (name "1ST AUXILIARY FIELD") "0.1W")
      )
      (libsource (lib "Automobile-ML") (part "ERE210RG110-SC"))
    )
    (comp (ref "R27")
      (value "10K")
      (footprint "Automobile-ML:SMDR0402")
      (description "RES SMD 10K OHM 5% 1/10W 0402")
      (fields
        (field (name "MANUFACTURER") "Panasonic Electronic Components")
        (field (name "VENDOR PART NUMBER") "P10KJCT-ND")
        (field (name "2ND AUXILIARY FIELD") "±5%")
        (field (name "1ST AUXILIARY FIELD") "0.1W")
      )
      (libsource (lib "Automobile-ML") (part "ERE10K0K110-SB"))
    )
    (comp (ref "R28")
      (value "10K")
      (footprint "Automobile-ML:SMDR0402")
      (description "RES SMD 10K OHM 5% 1/10W 0402")
      (fields
        (field (name "MANUFACTURER") "Panasonic Electronic Components")
        (field (name "VENDOR PART NUMBER") "P10KJCT-ND")
        (field (name "2ND AUXILIARY FIELD") "±5%")
        (field (name "1ST AUXILIARY FIELD") "0.1W")
      )
      (libsource (lib "Automobile-ML") (part "ERE10K0K110-SB"))
    )
    (comp (ref "R29")
      (value "4.7K")
      (footprint "SMDR0402")
      (description "RES SMD 4.7K OHM 1% 1/10W 0402")
      (fields
        (field (name "MANUFACTURER") "Panasonic Electronic Components")
        (field (name "VENDOR PART NUMBER") "P4.70KLCT-ND")
        (field (name "2ND AUXILIARY FIELD") "±1%")
        (field (name "1ST AUXILIARY FIELD") "0.1W")
      )
      (libsource (lib "Automobile-ML") (part "ERE4K70G110-SB"))
    )
    (comp (ref "R30")
      (value "DNP")
      (footprint "SMDR0402")
      (description "RES SMD 4.7K OHM 1% 1/10W 0402")
      (fields
        (field (name "MANUFACTURER") "Panasonic Electronic Components")
        (field (name "VENDOR PART NUMBER") "P4.70KLCT-ND")
        (field (name "2ND AUXILIARY FIELD") "±1%")
        (field (name "1ST AUXILIARY FIELD") "0.1W")
      )
      (libsource (lib "Automobile-ML") (part "ERE4K70G110-SB"))
    )
    (comp (ref "U1")
      (value "STM8AF6223PCU")
      (footprint "Automobile-ML:SOP65P640X120-20N")
      (description "IC MCU 8BIT 8KB FLASH 20TSSOP")
      (fields
        (field (name "MANUFACTURER") "STMicroelectronics")
        (field (name "INTERNAL PART NUMBER") "EICSTMTSSOP-20-1691")
      )
      (libsource (lib "Integrated_Master_Library (3)") (part "EICSTMTSSOP-20-1691"))
    )
    (comp (ref "U2")
      (value "TLE49641MXTSA1")
      (footprint "Integrated_Master_Library:SOT95P248X115-3N")
      (description "MAGNETIC SWITCH UNIPOLAR SOT23-3")
      (fields
        (field (name "MANUFACTURER") "Infineon Technologies")
        (field (name "VENDOR PART NUMBER") "TLE49641MXTSA1CT-ND")
      )
      (libsource (lib "Integrated_Master_Library") (part "EICITSOT23-3-1528"))
    )
    (comp (ref "U3")
      (value "TLE49641MXTSA1")
      (footprint "Integrated_Master_Library:SOT95P248X115-3N")
      (description "MAGNETIC SWITCH UNIPOLAR SOT23-3")
      (fields
        (field (name "MANUFACTURER") "Infineon Technologies")
        (field (name "VENDOR PART NUMBER") "TLE49641MXTSA1CT-ND")
      )
      (libsource (lib "Integrated_Master_Library") (part "EICITSOT23-3-1528"))
    )
    (comp (ref "U4")
      (value "TLE49641MXTSA1")
      (footprint "Integrated_Master_Library:SOT95P248X115-3N")
      (description "MAGNETIC SWITCH UNIPOLAR SOT23-3")
      (fields
        (field (name "MANUFACTURER") "Infineon Technologies")
        (field (name "VENDOR PART NUMBER") "TLE49641MXTSA1CT-ND")
      )
      (libsource (lib "Integrated_Master_Library") (part "EICITSOT23-3-1528"))
    )
    (comp (ref "U5")
      (value "TLE49641MXTSA1")
      (footprint "Integrated_Master_Library:SOT95P248X115-3N")
      (description "MAGNETIC SWITCH UNIPOLAR SOT23-3")
      (fields
        (field (name "MANUFACTURER") "Infineon Technologies")
        (field (name "VENDOR PART NUMBER") "TLE49641MXTSA1CT-ND")
      )
      (libsource (lib "Integrated_Master_Library") (part "EICITSOT23-3-1528"))
    )
    (comp (ref "U6")
      (value "TLE49641MXTSA1")
      (footprint "Integrated_Master_Library:SOT95P248X115-3N")
      (description "MAGNETIC SWITCH UNIPOLAR SOT23-3")
      (fields
        (field (name "MANUFACTURER") "Infineon Technologies")
        (field (name "VENDOR PART NUMBER") "TLE49641MXTSA1CT-ND")
      )
      (libsource (lib "Integrated_Master_Library") (part "EICITSOT23-3-1528"))
    )
    (comp (ref "U7")
      (value "TLE49641MXTSA1")
      (footprint "Integrated_Master_Library:SOT95P248X115-3N")
      (description "MAGNETIC SWITCH UNIPOLAR SOT23-3")
      (fields
        (field (name "MANUFACTURER") "Infineon Technologies")
        (field (name "VENDOR PART NUMBER") "TLE49641MXTSA1CT-ND")
      )
      (libsource (lib "Integrated_Master_Library") (part "EICITSOT23-3-1528"))
    )
    (comp (ref "U8")
      (value "TLE8366EV50XUMA1")
      (footprint "SOIC127P600X170_HS-9N")
      (description "IC REG BUCK 5V 1.8A 8DSO")
      (fields
        (field (name "MANUFACTURER") "Infineon Technologies")
        (field (name "INTERNAL PART NUMBER") "EICITSOIC-08-0001")
      )
      (libsource (lib "Automobile-ML") (part "EICITSOIC-08-0001"))
    )
    (comp (ref "U9")
      (value "PMDT670UPE,115")
      (footprint "SOTFL50P160X60-6N")
      (description "MOSFET 2P-CH 20V 0.55A SOT666")
      (fields
        (field (name "MANUFACTURER") "Nexperia USA Inc.")
        (field (name "INTERNAL PART NUMBER") "EICNUSOT666-06-0004")
      )
      (libsource (lib "Automobile-ML") (part "EICNUSOT666-06-0004"))
    )
    (comp (ref "U10")
      (value "PMDT670UPE,115")
      (footprint "SOTFL50P160X60-6N")
      (description "MOSFET 2P-CH 20V 0.55A SOT666")
      (fields
        (field (name "MANUFACTURER") "Nexperia USA Inc.")
        (field (name "INTERNAL PART NUMBER") "EICNUSOT666-06-0004")
      )
      (libsource (lib "Automobile-ML") (part "EICNUSOT666-06-0004"))
    )
  )
  (nets
    (net (code "1") (name "/AUTOMATIC") (class "Default")
      (node (ref "A") (pin "1") (pinfunction "1_1") (pintype "passive"))
      (node (ref "R13") (pin "2") (pinfunction "2_2") (pintype "passive"))
      (node (ref "U1") (pin "19") (pinfunction "PD2_(HS)/AIN3_[TIM5_CH3]_19") (pintype "passive"))
      (node (ref "U6") (pin "2") (pinfunction "Q_2") (pintype "output"))
    )
    (net (code "2") (name "/DEBUG") (class "Default")
      (node (ref "R29") (pin "1") (pinfunction "1_1") (pintype "passive"))
      (node (ref "R30") (pin "2") (pinfunction "2_2") (pintype "passive"))
      (node (ref "U1") (pin "17") (pinfunction "PC7_(HS)/SPI_MISO_[TIM1_CH2]_17") (pintype "passive"))
    )
    (net (code "3") (name "/M+") (class "Default")
      (node (ref "M+") (pin "1") (pinfunction "1_1") (pintype "passive"))
      (node (ref "R4") (pin "2") (pinfunction "2_2") (pintype "passive"))
      (node (ref "U1") (pin "1") (pinfunction "PD4(HS)/[LINUART_CK]_TIM5_CH1/BEEP_1") (pintype "passive"))
      (node (ref "U3") (pin "2") (pinfunction "Q_2") (pintype "output"))
    )
    (net (code "4") (name "/M-") (class "Default")
      (node (ref "M-") (pin "1") (pinfunction "1_1") (pintype "passive"))
      (node (ref "R14") (pin "2") (pinfunction "2_2") (pintype "passive"))
      (node (ref "U1") (pin "20") (pinfunction "PD3_(HS)/AIN4/TIM5_CH2/ADC_ETR_20") (pintype "passive"))
      (node (ref "U7") (pin "2") (pinfunction "Q_2") (pintype "output"))
    )
    (net (code "5") (name "/MANUAL") (class "Default")
      (node (ref "M") (pin "1") (pinfunction "1_1") (pintype "passive"))
      (node (ref "R10") (pin "2") (pinfunction "2_2") (pintype "passive"))
      (node (ref "U1") (pin "10") (pinfunction "PA3_(HS)/[SPI_NSS]_TIM5_CH3_10") (pintype "passive"))
      (node (ref "U5") (pin "2") (pinfunction "Q_2") (pintype "output"))
    )
    (net (code "6") (name "/NEUTRAL") (class "Default")
      (node (ref "N") (pin "1") (pinfunction "1_1") (pintype "passive"))
      (node (ref "R9") (pin "2") (pinfunction "2_2") (pintype "passive"))
      (node (ref "U1") (pin "16") (pinfunction "PC6_(HS)/SPI_MOSI_[TIM1_CH1]_16") (pintype "passive"))
      (node (ref "U4") (pin "2") (pinfunction "Q_2") (pintype "output"))
    )
    (net (code "7") (name "/REVERSE") (class "Default")
      (node (ref "R") (pin "1") (pinfunction "1_1") (pintype "passive"))
      (node (ref "R3") (pin "2") (pinfunction "2_2") (pintype "passive"))
      (node (ref "U1") (pin "13") (pinfunction "PC3_(HS)/TIM1_CH3_[TLI][TIM1_CH1N]_13") (pintype "passive"))
      (node (ref "U2") (pin "2") (pinfunction "Q_2") (pintype "output"))
    )
    (net (code "8") (name "/S1") (class "Default")
      (node (ref "U1") (pin "14") (pinfunction "PC4_(HS)/TIM1_CH4/CLK_CCO/AIN2_[TIM1_CH2N]_14") (pintype "passive"))
      (node (ref "U10") (pin "2") (pinfunction "G1_2") (pintype "passive"))
    )
    (net (code "9") (name "/S2") (class "Default")
      (node (ref "R27") (pin "1") (pinfunction "1_1") (pintype "passive"))
      (node (ref "U1") (pin "11") (pinfunction "PB5_(T)/I2C_SDA_[TIM1_BKIN]_11") (pintype "passive"))
      (node (ref "U10") (pin "5") (pinfunction "G2_5") (pintype "passive"))
    )
    (net (code "10") (name "/S3") (class "Default")
      (node (ref "R28") (pin "1") (pinfunction "1_1") (pintype "passive"))
      (node (ref "U1") (pin "12") (pinfunction "PB4_(T)/I2C_SCL_[ADC_ETR]_12") (pintype "passive"))
      (node (ref "U9") (pin "5") (pinfunction "G2_5") (pintype "passive"))
    )
    (net (code "11") (name "/S4") (class "Default")
      (node (ref "U1") (pin "15") (pinfunction "PC5_(HS)/SPI_SCK_[TIM5_CH1]_15") (pintype "passive"))
      (node (ref "U9") (pin "2") (pinfunction "G1_2") (pintype "passive"))
    )
    (net (code "12") (name "/SIGNAL1") (class "Default")
      (node (ref "A1") (pin "1") (pinfunction "1_1") (pintype "passive"))
      (node (ref "C23") (pin "2") (pinfunction "2_2") (pintype "passive"))
      (node (ref "D11") (pin "2") (pinfunction "CATHODE_2") (pintype "passive"))
      (node (ref "J3") (pin "4") (pinfunction "4_4") (pintype "passive"))
      (node (ref "R24") (pin "2") (pinfunction "2_2") (pintype "passive"))
      (node (ref "R26") (pin "1") (pinfunction "1_1") (pintype "passive"))
    )
    (net (code "13") (name "/SIGNAL2") (class "Default")
      (node (ref "A2") (pin "1") (pinfunction "1_1") (pintype "passive"))
      (node (ref "C21") (pin "2") (pinfunction "2_2") (pintype "passive"))
      (node (ref "D5") (pin "2") (pinfunction "CATHODE_2") (pintype "passive"))
      (node (ref "J3") (pin "5") (pinfunction "5_5") (pintype "passive"))
      (node (ref "R18") (pin "2") (pinfunction "2_2") (pintype "passive"))
      (node (ref "R20") (pin "1") (pinfunction "1_1") (pintype "passive"))
    )
    (net (code "14") (name "/SIGNAL3") (class "Default")
      (node (ref "A3") (pin "1") (pinfunction "1_1") (pintype "passive"))
      (node (ref "C20") (pin "2") (pinfunction "2_2") (pintype "passive"))
      (node (ref "D4") (pin "2") (pinfunction "CATHODE_2") (pintype "passive"))
      (node (ref "J3") (pin "6") (pinfunction "6_6") (pintype "passive"))
      (node (ref "R17") (pin "2") (pinfunction "2_2") (pintype "passive"))
      (node (ref "R19") (pin "1") (pinfunction "1_1") (pintype "passive"))
    )
    (net (code "15") (name "/SIGNAL4") (class "Default")
      (node (ref "A4") (pin "1") (pinfunction "1_1") (pintype "passive"))
      (node (ref "C22") (pin "2") (pinfunction "2_2") (pintype "passive"))
      (node (ref "D10") (pin "2") (pinfunction "CATHODE_2") (pintype "passive"))
      (node (ref "J3") (pin "2") (pinfunction "2_2") (pintype "passive"))
      (node (ref "R23") (pin "2") (pinfunction "2_2") (pintype "passive"))
      (node (ref "R25") (pin "1") (pinfunction "1_1") (pintype "passive"))
    )
    (net (code "16") (name "/SWIM") (class "Default")
      (node (ref "D12") (pin "2") (pinfunction "CATHODE_2") (pintype "passive"))
      (node (ref "J1") (pin "5") (pinfunction "5_5") (pintype "passive"))
      (node (ref "U1") (pin "18") (pinfunction "PD1_(HS)/SWIM_18") (pintype "passive"))
    )
    (net (code "17") (name "/UART_RX") (class "Default")
      (node (ref "D13") (pin "2") (pinfunction "CATHODE_2") (pintype "passive"))
      (node (ref "J1") (pin "4") (pinfunction "4_4") (pintype "passive"))
      (node (ref "U1") (pin "3") (pinfunction "PD6_(HS)/AIN6/LINUART_RX_3") (pintype "passive"))
    )
    (net (code "18") (name "/UART_TX") (class "Default")
      (node (ref "D14") (pin "2") (pinfunction "CATHODE_2") (pintype "passive"))
      (node (ref "J1") (pin "6") (pinfunction "6_6") (pintype "passive"))
      (node (ref "U1") (pin "2") (pinfunction "PD5_(HS)/AIN5/LINUART_TX_2") (pintype "passive"))
    )
    (net (code "19") (name "/nRESET") (class "Default")
      (node (ref "C6") (pin "1") (pinfunction "1_1") (pintype "passive"))
      (node (ref "R5") (pin "1") (pinfunction "1_1") (pintype "passive"))
      (node (ref "R6") (pin "2") (pinfunction "2_2") (pintype "passive"))
      (node (ref "U1") (pin "4") (pinfunction "NRST_4") (pintype "passive"))
    )
    (net (code "20") (name "GND") (class "Default")
      (node (ref "C1") (pin "2") (pinfunction "2_2") (pintype "passive"))
      (node (ref "C10") (pin "1") (pinfunction "1_1") (pintype "passive"))
      (node (ref "C11") (pin "1") (pinfunction "1_1") (pintype "passive"))
      (node (ref "C12") (pin "2") (pinfunction "2_2") (pintype "passive"))
      (node (ref "C14") (pin "1") (pinfunction "1_1") (pintype "passive"))
      (node (ref "C15") (pin "2") (pinfunction "2_2") (pintype "passive"))
      (node (ref "C18") (pin "2") (pinfunction "2_2") (pintype "passive"))
      (node (ref "C19") (pin "1") (pinfunction "1_1") (pintype "passive"))
      (node (ref "C2") (pin "1") (pinfunction "1_1") (pintype "passive"))
      (node (ref "C20") (pin "1") (pinfunction "1_1") (pintype "passive"))
      (node (ref "C21") (pin "1") (pinfunction "1_1") (pintype "passive"))
      (node (ref "C22") (pin "1") (pinfunction "1_1") (pintype "passive"))
      (node (ref "C23") (pin "1") (pinfunction "1_1") (pintype "passive"))
      (node (ref "C24") (pin "2") (pinfunction "2_2") (pintype "passive"))
      (node (ref "C25") (pin "2") (pinfunction "2_2") (pintype "passive"))
      (node (ref "C26") (pin "2") (pinfunction "2_2") (pintype "passive"))
      (node (ref "C3") (pin "2") (pinfunction "2_2") (pintype "passive"))
      (node (ref "C4") (pin "1") (pinfunction "1_1") (pintype "passive"))
      (node (ref "C5") (pin "1") (pinfunction "1_1") (pintype "passive"))
      (node (ref "C6") (pin "2") (pinfunction "2_2") (pintype "passive"))
      (node (ref "C7") (pin "1") (pinfunction "1_1") (pintype "passive"))
      (node (ref "C8") (pin "1") (pinfunction "1_1") (pintype "passive"))
      (node (ref "C9") (pin "1") (pinfunction "1_1") (pintype "passive"))
      (node (ref "D1") (pin "1") (pinfunction "Cathode_1") (pintype "passive"))
      (node (ref "D10") (pin "1") (pinfunction "ANODE_1") (pintype "passive"))
      (node (ref "D11") (pin "1") (pinfunction "ANODE_1") (pintype "passive"))
      (node (ref "D12") (pin "1") (pinfunction "ANODE_1") (pintype "passive"))
      (node (ref "D13") (pin "1") (pinfunction "ANODE_1") (pintype "passive"))
      (node (ref "D14") (pin "1") (pinfunction "ANODE_1") (pintype "passive"))
      (node (ref "D15") (pin "1") (pinfunction "ANODE_1") (pintype "passive"))
      (node (ref "D4") (pin "1") (pinfunction "ANODE_1") (pintype "passive"))
      (node (ref "D5") (pin "1") (pinfunction "ANODE_1") (pintype "passive"))
      (node (ref "D7") (pin "1") (pinfunction "ANODE_1") (pintype "passive"))
      (node (ref "GND") (pin "1") (pinfunction "1_1") (pintype "passive"))
      (node (ref "J1") (pin "3") (pinfunction "3_3") (pintype "passive"))
      (node (ref "J1") (pin "8") (pinfunction "8_8") (pintype "passive"))
      (node (ref "J3") (pin "1") (pinfunction "1_1") (pintype "passive"))
      (node (ref "R16") (pin "1") (pinfunction "1_1") (pintype "passive"))
      (node (ref "R19") (pin "2") (pinfunction "2_2") (pintype "passive"))
      (node (ref "R20") (pin "2") (pinfunction "2_2") (pintype "passive"))
      (node (ref "R25") (pin "2") (pinfunction "2_2") (pintype "passive"))
      (node (ref "R26") (pin "2") (pinfunction "2_2") (pintype "passive"))
      (node (ref "R30") (pin "1") (pinfunction "1_1") (pintype "passive"))
      (node (ref "U1") (pin "7") (pinfunction "VSS_7") (pintype "passive"))
      (node (ref "U2") (pin "3") (pinfunction "GND_3") (pintype "power_in"))
      (node (ref "U3") (pin "3") (pinfunction "GND_3") (pintype "power_in"))
      (node (ref "U4") (pin "3") (pinfunction "GND_3") (pintype "power_in"))
      (node (ref "U5") (pin "3") (pinfunction "GND_3") (pintype "power_in"))
      (node (ref "U6") (pin "3") (pinfunction "GND_3") (pintype "power_in"))
      (node (ref "U7") (pin "3") (pinfunction "GND_3") (pintype "power_in"))
      (node (ref "U8") (pin "1") (pinfunction "SYNC_1") (pintype "passive"))
      (node (ref "U8") (pin "2") (pinfunction "GND_2") (pintype "passive"))
      (node (ref "U8") (pin "9") (pinfunction "EPAD_9") (pintype "passive"))
    )
    (net (code "21") (name "Net-(C13-Pad2)") (class "Default")
      (node (ref "C13") (pin "2") (pinfunction "2_2") (pintype "passive"))
      (node (ref "R16") (pin "2") (pinfunction "2_2") (pintype "passive"))
    )
    (net (code "22") (name "Net-(D1-Anode)") (class "Default")
      (node (ref "C16") (pin "2") (pinfunction "2_2") (pintype "passive"))
      (node (ref "D1") (pin "2") (pinfunction "Anode_2") (pintype "passive"))
      (node (ref "L1") (pin "1") (pinfunction "1_1") (pintype "passive"))
      (node (ref "U8") (pin "6") (pinfunction "BUO_6") (pintype "passive"))
    )
    (net (code "23") (name "Net-(D2-ANODE)") (class "Default")
      (node (ref "D2") (pin "2") (pinfunction "ANODE_2") (pintype "passive"))
      (node (ref "U9") (pin "3") (pinfunction "D2_3") (pintype "passive"))
    )
    (net (code "24") (name "Net-(D2-CATHODE)") (class "Default")
      (node (ref "D2") (pin "1") (pinfunction "CATHODE_1") (pintype "passive"))
      (node (ref "R17") (pin "1") (pinfunction "1_1") (pintype "passive"))
    )
    (net (code "25") (name "Net-(D3-ANODE)") (class "Default")
      (node (ref "D3") (pin "2") (pinfunction "ANODE_2") (pintype "passive"))
      (node (ref "U10") (pin "3") (pinfunction "D2_3") (pintype "passive"))
    )
    (net (code "26") (name "Net-(D3-CATHODE)") (class "Default")
      (node (ref "D3") (pin "1") (pinfunction "CATHODE_1") (pintype "passive"))
      (node (ref "R18") (pin "1") (pinfunction "1_1") (pintype "passive"))
    )
    (net (code "27") (name "Net-(D6-Anode)") (class "Default")
      (node (ref "D6") (pin "2") (pinfunction "Anode_2") (pintype "passive"))
      (node (ref "D7") (pin "2") (pinfunction "CATHODE_2") (pintype "passive"))
      (node (ref "J3") (pin "3") (pinfunction "3_3") (pintype "passive"))
    )
    (net (code "28") (name "Net-(D8-ANODE)") (class "Default")
      (node (ref "D8") (pin "2") (pinfunction "ANODE_2") (pintype "passive"))
      (node (ref "U9") (pin "6") (pinfunction "D1_6") (pintype "passive"))
    )
    (net (code "29") (name "Net-(D8-CATHODE)") (class "Default")
      (node (ref "D8") (pin "1") (pinfunction "CATHODE_1") (pintype "passive"))
      (node (ref "R23") (pin "1") (pinfunction "1_1") (pintype "passive"))
    )
    (net (code "30") (name "Net-(D9-ANODE)") (class "Default")
      (node (ref "D9") (pin "2") (pinfunction "ANODE_2") (pintype "passive"))
      (node (ref "U10") (pin "6") (pinfunction "D1_6") (pintype "passive"))
    )
    (net (code "31") (name "Net-(D9-CATHODE)") (class "Default")
      (node (ref "D9") (pin "1") (pinfunction "CATHODE_1") (pintype "passive"))
      (node (ref "R24") (pin "1") (pinfunction "1_1") (pintype "passive"))
    )
    (net (code "32") (name "Net-(D15-CATHODE)") (class "Default")
      (node (ref "D15") (pin "2") (pinfunction "CATHODE_2") (pintype "passive"))
      (node (ref "J1") (pin "7") (pinfunction "7_7") (pintype "passive"))
      (node (ref "R6") (pin "1") (pinfunction "1_1") (pintype "passive"))
    )
    (net (code "33") (name "Net-(U1-VCAP)") (class "Default")
      (node (ref "C3") (pin "1") (pinfunction "1_1") (pintype "passive"))
      (node (ref "U1") (pin "8") (pinfunction "VCAP_8") (pintype "passive"))
    )
    (net (code "34") (name "Net-(U2-VDD)") (class "Default")
      (node (ref "C4") (pin "2") (pinfunction "2_2") (pintype "passive"))
      (node (ref "R1") (pin "2") (pinfunction "2_2") (pintype "passive"))
      (node (ref "U2") (pin "1") (pinfunction "VDD_1") (pintype "power_in"))
    )
    (net (code "35") (name "Net-(U3-VDD)") (class "Default")
      (node (ref "C5") (pin "2") (pinfunction "2_2") (pintype "passive"))
      (node (ref "R2") (pin "2") (pinfunction "2_2") (pintype "passive"))
      (node (ref "U3") (pin "1") (pinfunction "VDD_1") (pintype "power_in"))
    )
    (net (code "36") (name "Net-(U4-VDD)") (class "Default")
      (node (ref "C7") (pin "2") (pinfunction "2_2") (pintype "passive"))
      (node (ref "R7") (pin "2") (pinfunction "2_2") (pintype "passive"))
      (node (ref "U4") (pin "1") (pinfunction "VDD_1") (pintype "power_in"))
    )
    (net (code "37") (name "Net-(U5-VDD)") (class "Default")
      (node (ref "C8") (pin "2") (pinfunction "2_2") (pintype "passive"))
      (node (ref "R8") (pin "2") (pinfunction "2_2") (pintype "passive"))
      (node (ref "U5") (pin "1") (pinfunction "VDD_1") (pintype "power_in"))
    )
    (net (code "38") (name "Net-(U6-VDD)") (class "Default")
      (node (ref "C9") (pin "2") (pinfunction "2_2") (pintype "passive"))
      (node (ref "R11") (pin "2") (pinfunction "2_2") (pintype "passive"))
      (node (ref "U6") (pin "1") (pinfunction "VDD_1") (pintype "power_in"))
    )
    (net (code "39") (name "Net-(U7-VDD)") (class "Default")
      (node (ref "C10") (pin "2") (pinfunction "2_2") (pintype "passive"))
      (node (ref "R12") (pin "2") (pinfunction "2_2") (pintype "passive"))
      (node (ref "U7") (pin "1") (pinfunction "VDD_1") (pintype "power_in"))
    )
    (net (code "40") (name "Net-(U8-BDS)") (class "Default")
      (node (ref "C16") (pin "1") (pinfunction "1_1") (pintype "passive"))
      (node (ref "U8") (pin "5") (pinfunction "BDS_5") (pintype "passive"))
    )
    (net (code "41") (name "Net-(U8-COMP)") (class "Default")
      (node (ref "C13") (pin "1") (pinfunction "1_1") (pintype "passive"))
      (node (ref "C24") (pin "1") (pinfunction "1_1") (pintype "passive"))
      (node (ref "U8") (pin "3") (pinfunction "COMP_3") (pintype "passive"))
    )
    (net (code "42") (name "Net-(U8-EN)") (class "Default")
      (node (ref "R15") (pin "1") (pinfunction "1_1") (pintype "passive"))
      (node (ref "U8") (pin "7") (pinfunction "EN_7") (pintype "passive"))
    )
    (net (code "43") (name "Net-(U8-FB)") (class "Default")
      (node (ref "C14") (pin "2") (pinfunction "2_2") (pintype "passive"))
      (node (ref "C19") (pin "2") (pinfunction "2_2") (pintype "passive"))
      (node (ref "FB1") (pin "1") (pinfunction "1_1") (pintype "passive"))
      (node (ref "L1") (pin "2") (pinfunction "2_2") (pintype "passive"))
      (node (ref "U8") (pin "4") (pinfunction "FB_4") (pintype "passive"))
    )
    (net (code "44") (name "VCC_5V") (class "Default")
      (node (ref "5V") (pin "1") (pinfunction "1_1") (pintype "passive"))
      (node (ref "C1") (pin "1") (pinfunction "1_1") (pintype "passive"))
      (node (ref "C15") (pin "1") (pinfunction "1_1") (pintype "passive"))
      (node (ref "C2") (pin "2") (pinfunction "2_2") (pintype "passive"))
      (node (ref "C25") (pin "1") (pinfunction "1_1") (pintype "passive"))
      (node (ref "C26") (pin "1") (pinfunction "1_1") (pintype "passive"))
      (node (ref "FB1") (pin "2") (pinfunction "2_2") (pintype "passive"))
      (node (ref "J1") (pin "1") (pinfunction "1_1") (pintype "passive"))
      (node (ref "J1") (pin "2") (pinfunction "2_2") (pintype "passive"))
      (node (ref "R1") (pin "1") (pinfunction "1_1") (pintype "passive"))
      (node (ref "R10") (pin "1") (pinfunction "1_1") (pintype "passive"))
      (node (ref "R11") (pin "1") (pinfunction "1_1") (pintype "passive"))
      (node (ref "R12") (pin "1") (pinfunction "1_1") (pintype "passive"))
      (node (ref "R13") (pin "1") (pinfunction "1_1") (pintype "passive"))
      (node (ref "R14") (pin "1") (pinfunction "1_1") (pintype "passive"))
      (node (ref "R2") (pin "1") (pinfunction "1_1") (pintype "passive"))
      (node (ref "R27") (pin "2") (pinfunction "2_2") (pintype "passive"))
      (node (ref "R28") (pin "2") (pinfunction "2_2") (pintype "passive"))
      (node (ref "R29") (pin "2") (pinfunction "2_2") (pintype "passive"))
      (node (ref "R3") (pin "1") (pinfunction "1_1") (pintype "passive"))
      (node (ref "R4") (pin "1") (pinfunction "1_1") (pintype "passive"))
      (node (ref "R5") (pin "2") (pinfunction "2_2") (pintype "passive"))
      (node (ref "R7") (pin "1") (pinfunction "1_1") (pintype "passive"))
      (node (ref "R8") (pin "1") (pinfunction "1_1") (pintype "passive"))
      (node (ref "R9") (pin "1") (pinfunction "1_1") (pintype "passive"))
      (node (ref "U1") (pin "9") (pinfunction "VDD_9") (pintype "passive"))
      (node (ref "U10") (pin "1") (pinfunction "S1_1") (pintype "passive"))
      (node (ref "U10") (pin "4") (pinfunction "S2_4") (pintype "passive"))
      (node (ref "U9") (pin "1") (pinfunction "S1_1") (pintype "passive"))
      (node (ref "U9") (pin "4") (pinfunction "S2_4") (pintype "passive"))
    )
    (net (code "45") (name "VCC_IN") (class "Default")
      (node (ref "C11") (pin "2") (pinfunction "2_2") (pintype "passive"))
      (node (ref "C12") (pin "1") (pinfunction "1_1") (pintype "passive"))
      (node (ref "C18") (pin "1") (pinfunction "1_1") (pintype "passive"))
      (node (ref "D6") (pin "1") (pinfunction "Cathode_1") (pintype "passive"))
      (node (ref "R15") (pin "2") (pinfunction "2_2") (pintype "passive"))
      (node (ref "U8") (pin "8") (pinfunction "VS_8") (pintype "passive"))
    )
    (net (code "46") (name "unconnected-(FID1-Pad0)") (class "Default")
      (node (ref "FID1") (pin "0") (pinfunction "0_0") (pintype "passive+no_connect"))
    )
    (net (code "47") (name "unconnected-(FID2-Pad0)") (class "Default")
      (node (ref "FID2") (pin "0") (pinfunction "0_0") (pintype "passive+no_connect"))
    )
    (net (code "48") (name "unconnected-(FID3-Pad0)") (class "Default")
      (node (ref "FID3") (pin "0") (pinfunction "0_0") (pintype "passive+no_connect"))
    )
    (net (code "49") (name "unconnected-(FID4-Pad0)") (class "Default")
      (node (ref "FID4") (pin "0") (pinfunction "0_0") (pintype "passive+no_connect"))
    )
    (net (code "50") (name "unconnected-(U1-PA1{slash}OSCIN-Pad5)") (class "Default")
      (node (ref "U1") (pin "5") (pinfunction "PA1/OSCIN_5") (pintype "passive+no_connect"))
    )
    (net (code "51") (name "unconnected-(U1-PA2{slash}OSCOUT-Pad6)") (class "Default")
      (node (ref "U1") (pin "6") (pinfunction "PA2/OSCOUT_6") (pintype "passive+no_connect"))
    )
  )
)
